# rev15.net
KiCad netlist of a schematic drawn in EAGLE
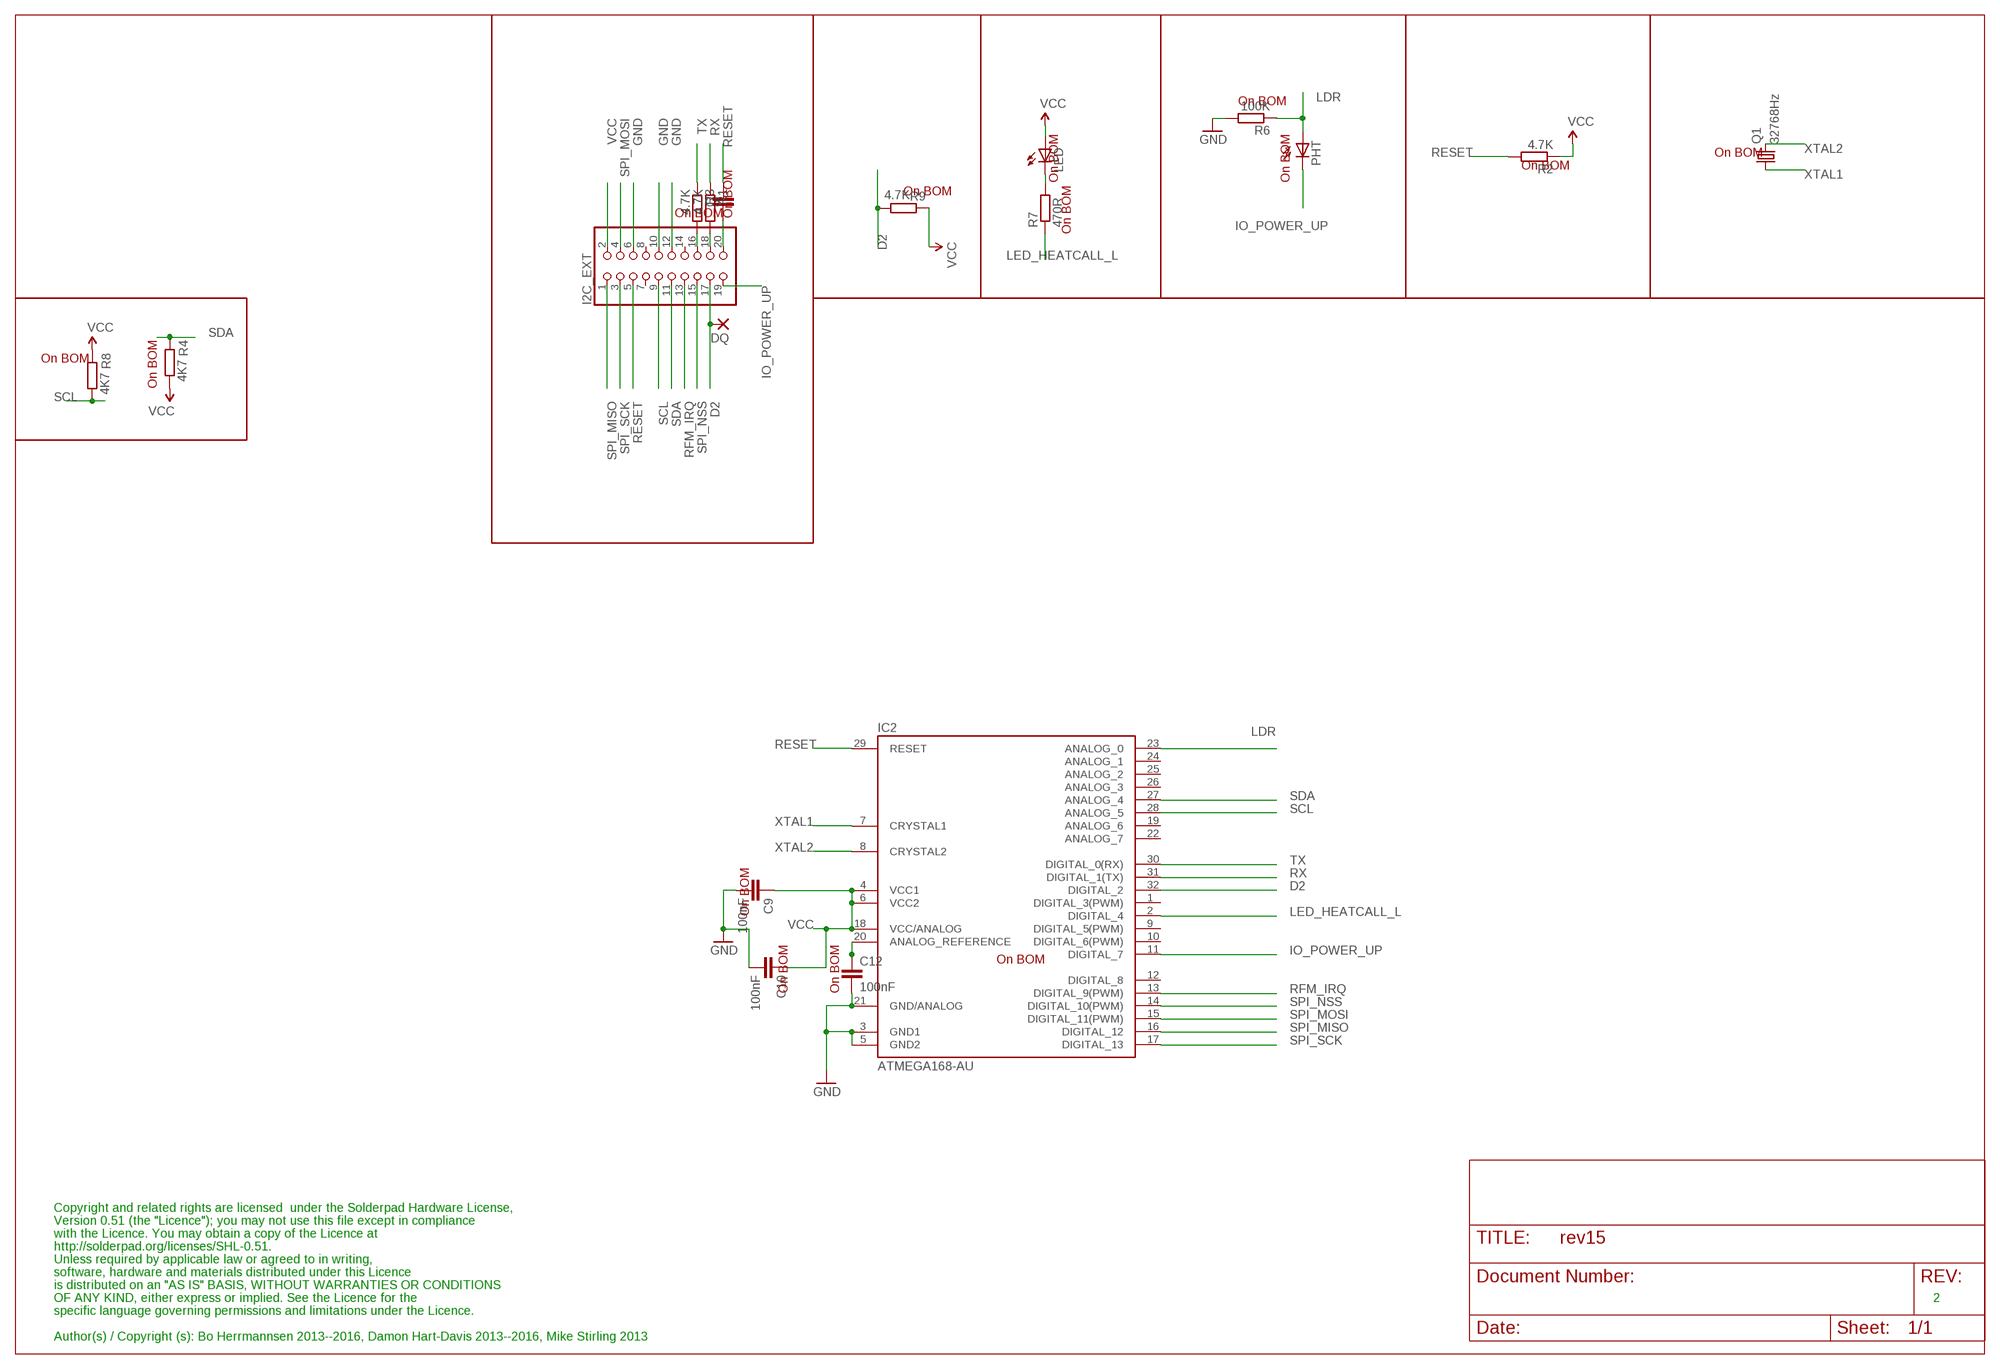
[diagram p0: schematic, sheet 1]

(export (version "E")
  (design (tool "Eeschema 10.0.6"))
  (components
    (comp (ref "C5")
      (value "100nF")
      (footprint "eagle-import:C0603")
      (libsource (lib "eagle-import") (part "C-EUC0603"))
    )
    (comp (ref "C9")
      (value "100nF")
      (footprint "eagle-import:C0603")
      (libsource (lib "eagle-import") (part "C-EUC0603"))
    )
    (comp (ref "C10")
      (value "100nF")
      (footprint "eagle-import:C0603")
      (libsource (lib "eagle-import") (part "C-EUC0603"))
    )
    (comp (ref "C12")
      (value "100nF")
      (footprint "eagle-import:C0603")
      (libsource (lib "eagle-import") (part "C-EUC0603"))
    )
    (comp (ref "DQ")
      (value "2,15/1,0")
      (footprint "eagle-import:2,15_1,0")
      (libsource (lib "eagle-import") (part "2,15/1,0"))
    )
    (comp (ref "I2C_EXT")
      (value "PINHD-2X10")
      (footprint "eagle-import:2X10")
      (libsource (lib "eagle-import") (part "PINHD-2X10"))
    )
    (comp (ref "IC2")
      (value "ATMEGA168-AU")
      (footprint "eagle-import:TQFP32-08")
      (libsource (lib "eagle-import") (part "ATMEGA168-AU"))
    )
    (comp (ref "LED")
      (value "LEDCHIP-LED0603")
      (footprint "eagle-import:CHIP-LED0603")
      (libsource (lib "eagle-import") (part "LEDCHIP-LED0603"))
    )
    (comp (ref "PHT")
      (value "BPX65")
      (footprint "eagle-import:BPX65")
      (fields (field (name "MPN") "BPX65."))
      (libsource (lib "eagle-import") (part "BPX65"))
    )
    (comp (ref "Q1")
      (value "32768Hz")
      (footprint "eagle-import:MC-306")
      (fields (field (name "MPN") "MC-306 60.0KHZ  100PPM ,12.5PF"))
      (libsource (lib "eagle-import") (part "MC-306"))
    )
    (comp (ref "R1")
      (value "4.7K")
      (footprint "eagle-import:R0603")
      (libsource (lib "eagle-import") (part "R-EU_R0603"))
    )
    (comp (ref "R2")
      (value "4.7K")
      (footprint "eagle-import:R0603")
      (libsource (lib "eagle-import") (part "R-EU_R0603"))
    )
    (comp (ref "R3")
      (value "4.7K")
      (footprint "eagle-import:R0603")
      (libsource (lib "eagle-import") (part "R-EU_R0603"))
    )
    (comp (ref "R4")
      (value "4K7")
      (footprint "eagle-import:R0603")
      (libsource (lib "eagle-import") (part "R-EU_R0603"))
    )
    (comp (ref "R6")
      (value "100K")
      (footprint "eagle-import:R0603")
      (libsource (lib "eagle-import") (part "R-EU_R0603"))
    )
    (comp (ref "R7")
      (value "470R")
      (footprint "eagle-import:R0603")
      (libsource (lib "eagle-import") (part "R-EU_R0603"))
    )
    (comp (ref "R8")
      (value "4K7")
      (footprint "eagle-import:R0603")
      (libsource (lib "eagle-import") (part "R-EU_R0603"))
    )
    (comp (ref "R9")
      (value "4.7K")
      (footprint "eagle-import:R0603")
      (libsource (lib "eagle-import") (part "R-EU_R0603"))
    )
  )
  (nets
    (net (code "1") (name "/D2") (class "Default")
      (node (ref "DQ") (pin "1") (pinfunction "P_1") (pintype "passive"))
      (node (ref "I2C_EXT") (pin "17") (pinfunction "17_17") (pintype "passive"))
      (node (ref "IC2") (pin "32") (pinfunction "DIGITAL_2_32") (pintype "bidirectional"))
      (node (ref "R9") (pin "1") (pinfunction "1_1") (pintype "passive"))
    )
    (net (code "2") (name "/IO_POWER_UP") (class "Default")
      (node (ref "I2C_EXT") (pin "19") (pinfunction "19_19") (pintype "passive"))
      (node (ref "IC2") (pin "11") (pinfunction "DIGITAL_7_11") (pintype "bidirectional"))
      (node (ref "PHT") (pin "K") (pinfunction "C_K") (pintype "passive"))
    )
    (net (code "3") (name "/LDR") (class "Default")
      (node (ref "IC2") (pin "23") (pinfunction "ANALOG_0_23") (pintype "bidirectional"))
      (node (ref "PHT") (pin "A") (pinfunction "A_A") (pintype "passive"))
      (node (ref "R6") (pin "1") (pinfunction "1_1") (pintype "passive"))
    )
    (net (code "4") (name "/LED_HEATCALL_L") (class "Default")
      (node (ref "IC2") (pin "2") (pinfunction "DIGITAL_4_2") (pintype "bidirectional"))
      (node (ref "R7") (pin "1") (pinfunction "1_1") (pintype "passive"))
    )
    (net (code "5") (name "/RESET") (class "Default")
      (node (ref "C5") (pin "1") (pinfunction "1_1") (pintype "passive"))
      (node (ref "I2C_EXT") (pin "5") (pinfunction "5_5") (pintype "passive"))
      (node (ref "IC2") (pin "29") (pinfunction "RESET_29") (pintype "bidirectional"))
      (node (ref "R2") (pin "2") (pinfunction "2_2") (pintype "passive"))
    )
    (net (code "6") (name "/RFM_IRQ") (class "Default")
      (node (ref "I2C_EXT") (pin "13") (pinfunction "13_13") (pintype "passive"))
      (node (ref "IC2") (pin "13") (pinfunction "DIGITAL_9(PWM)_13") (pintype "bidirectional"))
    )
    (net (code "7") (name "/RX") (class "Default")
      (node (ref "IC2") (pin "31") (pinfunction "DIGITAL_1(TX)_31") (pintype "bidirectional"))
      (node (ref "R1") (pin "1") (pinfunction "1_1") (pintype "passive"))
    )
    (net (code "8") (name "/SCL") (class "Default")
      (node (ref "I2C_EXT") (pin "9") (pinfunction "9_9") (pintype "passive"))
      (node (ref "IC2") (pin "28") (pinfunction "ANALOG_5_28") (pintype "bidirectional"))
      (node (ref "R8") (pin "1") (pinfunction "1_1") (pintype "passive"))
    )
    (net (code "9") (name "/SDA") (class "Default")
      (node (ref "I2C_EXT") (pin "11") (pinfunction "11_11") (pintype "passive"))
      (node (ref "IC2") (pin "27") (pinfunction "ANALOG_4_27") (pintype "bidirectional"))
      (node (ref "R4") (pin "2") (pinfunction "2_2") (pintype "passive"))
    )
    (net (code "10") (name "/SPI_MISO") (class "Default")
      (node (ref "I2C_EXT") (pin "1") (pinfunction "1_1") (pintype "passive"))
      (node (ref "IC2") (pin "16") (pinfunction "DIGITAL_12_16") (pintype "bidirectional"))
    )
    (net (code "11") (name "/SPI_MOSI") (class "Default")
      (node (ref "I2C_EXT") (pin "4") (pinfunction "4_4") (pintype "passive"))
      (node (ref "IC2") (pin "15") (pinfunction "DIGITAL_11(PWM)_15") (pintype "bidirectional"))
    )
    (net (code "12") (name "/SPI_NSS") (class "Default")
      (node (ref "I2C_EXT") (pin "15") (pinfunction "15_15") (pintype "passive"))
      (node (ref "IC2") (pin "14") (pinfunction "DIGITAL_10(PWM)_14") (pintype "bidirectional"))
    )
    (net (code "13") (name "/SPI_SCK") (class "Default")
      (node (ref "I2C_EXT") (pin "3") (pinfunction "3_3") (pintype "passive"))
      (node (ref "IC2") (pin "17") (pinfunction "DIGITAL_13_17") (pintype "bidirectional"))
    )
    (net (code "14") (name "/TX") (class "Default")
      (node (ref "IC2") (pin "30") (pinfunction "DIGITAL_0(RX)_30") (pintype "bidirectional"))
      (node (ref "R3") (pin "1") (pinfunction "1_1") (pintype "passive"))
    )
    (net (code "15") (name "/XTAL1") (class "Default")
      (node (ref "IC2") (pin "7") (pinfunction "CRYSTAL1_7") (pintype "bidirectional"))
      (node (ref "Q1") (pin "1") (pinfunction "1_1") (pintype "passive"))
    )
    (net (code "16") (name "/XTAL2") (class "Default")
      (node (ref "IC2") (pin "8") (pinfunction "CRYSTAL2_8") (pintype "bidirectional"))
      (node (ref "Q1") (pin "4") (pinfunction "2_4") (pintype "passive"))
    )
    (net (code "17") (name "GND") (class "Default")
      (node (ref "C10") (pin "2") (pinfunction "2_2") (pintype "passive"))
      (node (ref "C12") (pin "2") (pinfunction "2_2") (pintype "passive"))
      (node (ref "C9") (pin "2") (pinfunction "2_2") (pintype "passive"))
      (node (ref "I2C_EXT") (pin "10") (pinfunction "10_10") (pintype "passive"))
      (node (ref "I2C_EXT") (pin "12") (pinfunction "12_12") (pintype "passive"))
      (node (ref "I2C_EXT") (pin "6") (pinfunction "6_6") (pintype "passive"))
      (node (ref "IC2") (pin "21") (pinfunction "GND/ANALOG_21") (pintype "power_in"))
      (node (ref "IC2") (pin "3") (pinfunction "GND1_3") (pintype "power_in"))
      (node (ref "IC2") (pin "5") (pinfunction "GND2_5") (pintype "power_in"))
      (node (ref "R6") (pin "2") (pinfunction "2_2") (pintype "passive"))
    )
    (net (code "18") (name "Net-(C5-Pad2)") (class "Default")
      (node (ref "C5") (pin "2") (pinfunction "2_2") (pintype "passive"))
      (node (ref "I2C_EXT") (pin "20") (pinfunction "20_20") (pintype "passive"))
    )
    (net (code "19") (name "Net-(I2C_EXT-Pad16)") (class "Default")
      (node (ref "I2C_EXT") (pin "16") (pinfunction "16_16") (pintype "passive"))
      (node (ref "R3") (pin "2") (pinfunction "2_2") (pintype "passive"))
    )
    (net (code "20") (name "Net-(I2C_EXT-Pad18)") (class "Default")
      (node (ref "I2C_EXT") (pin "18") (pinfunction "18_18") (pintype "passive"))
      (node (ref "R1") (pin "2") (pinfunction "2_2") (pintype "passive"))
    )
    (net (code "21") (name "Net-(IC2-ANALOG_REFERENCE)") (class "Default")
      (node (ref "C12") (pin "1") (pinfunction "1_1") (pintype "passive"))
      (node (ref "IC2") (pin "20") (pinfunction "ANALOG_REFERENCE_20") (pintype "passive"))
    )
    (net (code "22") (name "Net-(LED-PadC)") (class "Default")
      (node (ref "LED") (pin "C") (pinfunction "C_C") (pintype "passive"))
      (node (ref "R7") (pin "2") (pinfunction "2_2") (pintype "passive"))
    )
    (net (code "23") (name "VCC") (class "Default")
      (node (ref "C10") (pin "1") (pinfunction "1_1") (pintype "passive"))
      (node (ref "C9") (pin "1") (pinfunction "1_1") (pintype "passive"))
      (node (ref "I2C_EXT") (pin "2") (pinfunction "2_2") (pintype "passive"))
      (node (ref "IC2") (pin "18") (pinfunction "VCC/ANALOG_18") (pintype "passive"))
      (node (ref "IC2") (pin "4") (pinfunction "VCC1_4") (pintype "power_in"))
      (node (ref "IC2") (pin "6") (pinfunction "VCC2_6") (pintype "power_in"))
      (node (ref "LED") (pin "A") (pinfunction "A_A") (pintype "passive"))
      (node (ref "R2") (pin "1") (pinfunction "1_1") (pintype "passive"))
      (node (ref "R4") (pin "1") (pinfunction "1_1") (pintype "passive"))
      (node (ref "R8") (pin "2") (pinfunction "2_2") (pintype "passive"))
      (node (ref "R9") (pin "2") (pinfunction "2_2") (pintype "passive"))
    )
    (net (code "24") (name "unconnected-(I2C_EXT-Pad7)") (class "Default")
      (node (ref "I2C_EXT") (pin "7") (pinfunction "7_7") (pintype "passive"))
    )
    (net (code "25") (name "unconnected-(I2C_EXT-Pad8)") (class "Default")
      (node (ref "I2C_EXT") (pin "8") (pinfunction "8_8") (pintype "passive"))
    )
    (net (code "26") (name "unconnected-(I2C_EXT-Pad14)") (class "Default")
      (node (ref "I2C_EXT") (pin "14") (pinfunction "14_14") (pintype "passive"))
    )
    (net (code "27") (name "unconnected-(IC2-ANALOG_1-Pad24)") (class "Default")
      (node (ref "IC2") (pin "24") (pinfunction "ANALOG_1_24") (pintype "bidirectional"))
    )
    (net (code "28") (name "unconnected-(IC2-ANALOG_2-Pad25)") (class "Default")
      (node (ref "IC2") (pin "25") (pinfunction "ANALOG_2_25") (pintype "bidirectional"))
    )
    (net (code "29") (name "unconnected-(IC2-ANALOG_3-Pad26)") (class "Default")
      (node (ref "IC2") (pin "26") (pinfunction "ANALOG_3_26") (pintype "bidirectional"))
    )
    (net (code "30") (name "unconnected-(IC2-ANALOG_6-Pad19)") (class "Default")
      (node (ref "IC2") (pin "19") (pinfunction "ANALOG_6_19") (pintype "passive"))
    )
    (net (code "31") (name "unconnected-(IC2-ANALOG_7-Pad22)") (class "Default")
      (node (ref "IC2") (pin "22") (pinfunction "ANALOG_7_22") (pintype "passive"))
    )
    (net (code "32") (name "unconnected-(IC2-DIGITAL_3(PWM)-Pad1)") (class "Default")
      (node (ref "IC2") (pin "1") (pinfunction "DIGITAL_3(PWM)_1") (pintype "bidirectional"))
    )
    (net (code "33") (name "unconnected-(IC2-DIGITAL_5(PWM)-Pad9)") (class "Default")
      (node (ref "IC2") (pin "9") (pinfunction "DIGITAL_5(PWM)_9") (pintype "bidirectional"))
    )
    (net (code "34") (name "unconnected-(IC2-DIGITAL_6(PWM)-Pad10)") (class "Default")
      (node (ref "IC2") (pin "10") (pinfunction "DIGITAL_6(PWM)_10") (pintype "bidirectional"))
    )
    (net (code "35") (name "unconnected-(IC2-DIGITAL_8-Pad12)") (class "Default")
      (node (ref "IC2") (pin "12") (pinfunction "DIGITAL_8_12") (pintype "bidirectional"))
    )
  )
)
